# Button.net
KiCad netlist of a schematic drawn in EAGLE
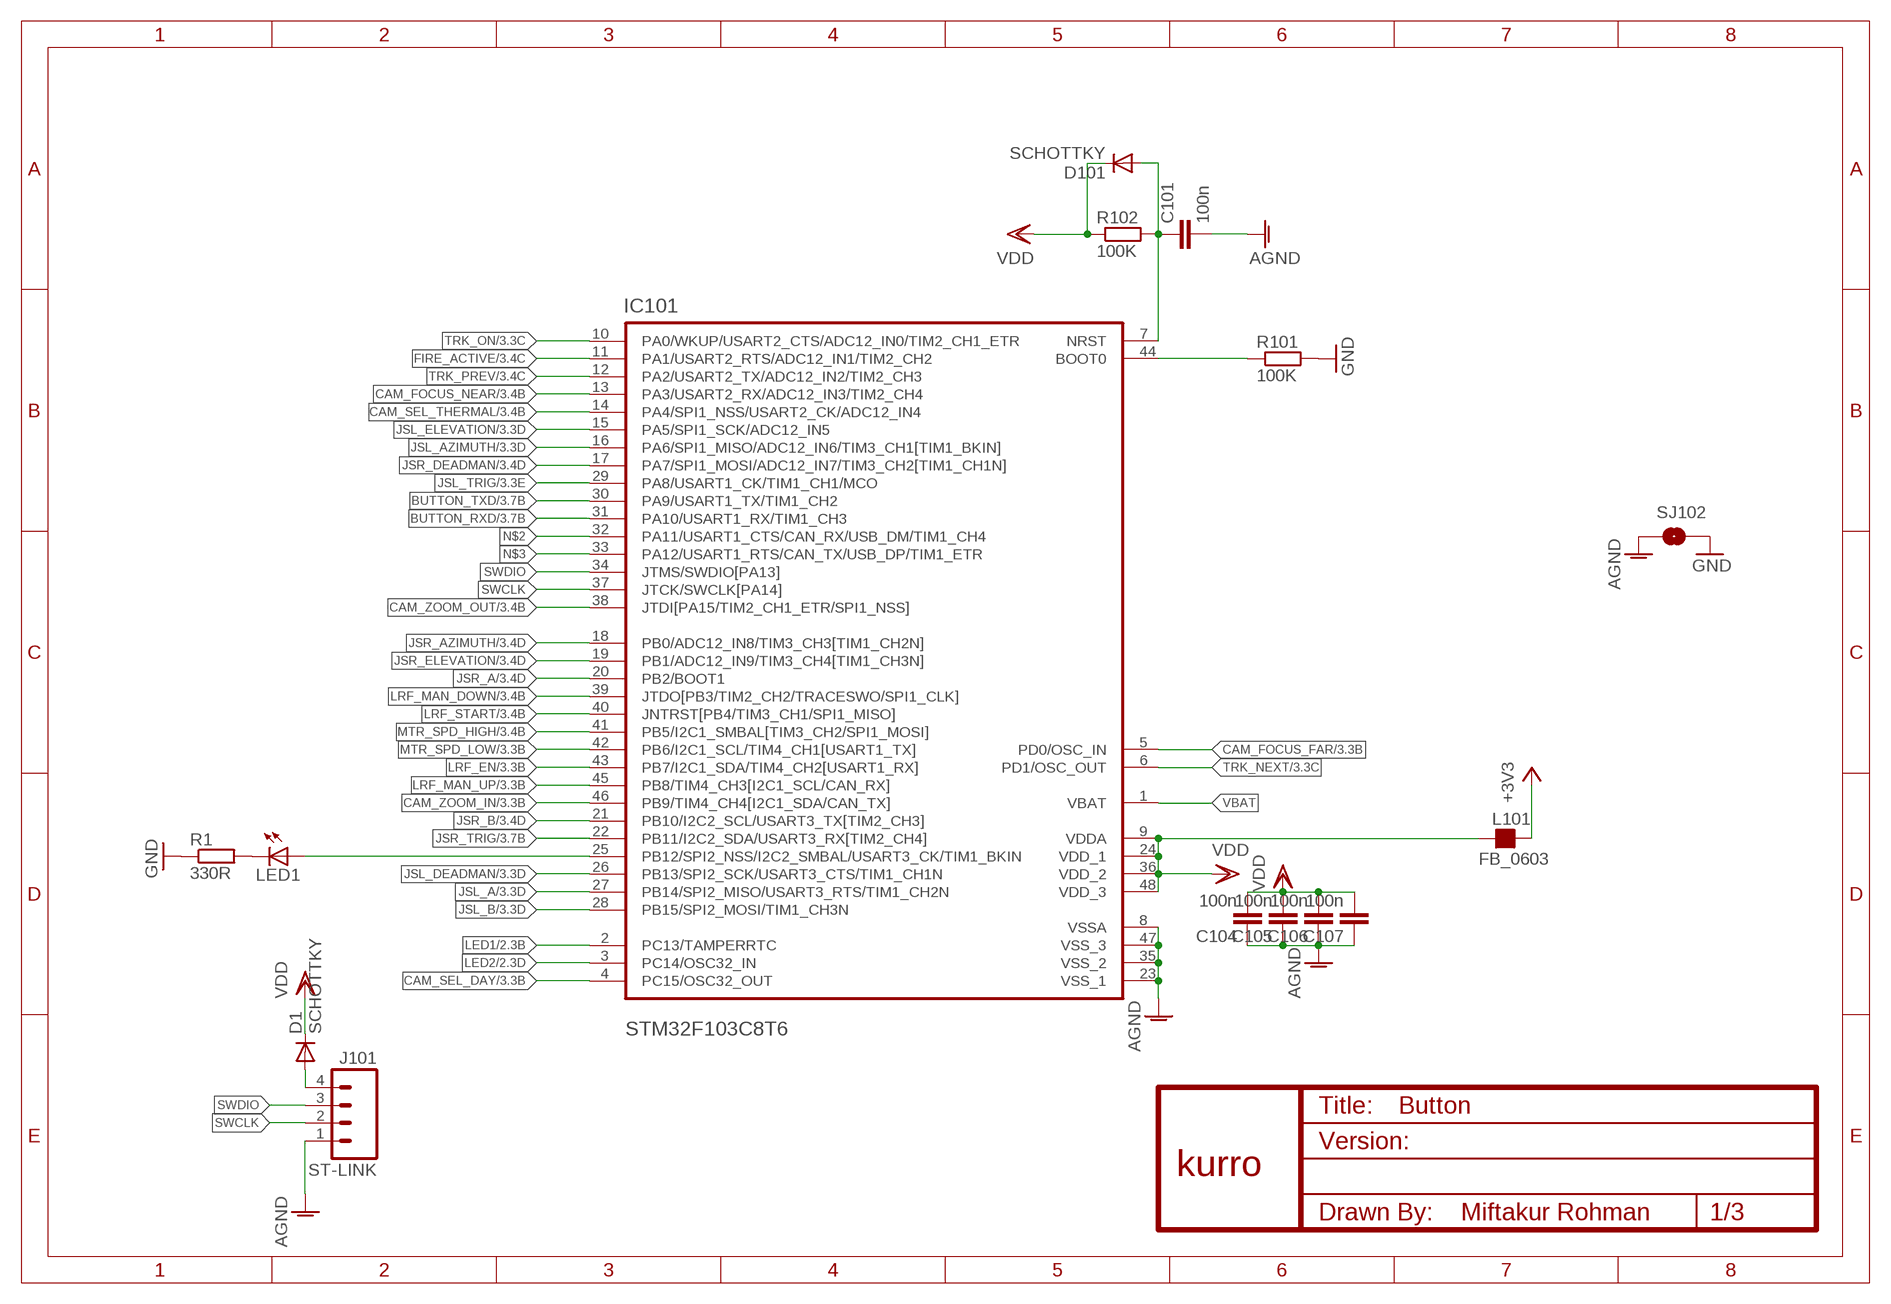
[diagram p0: schematic, sheet 1]
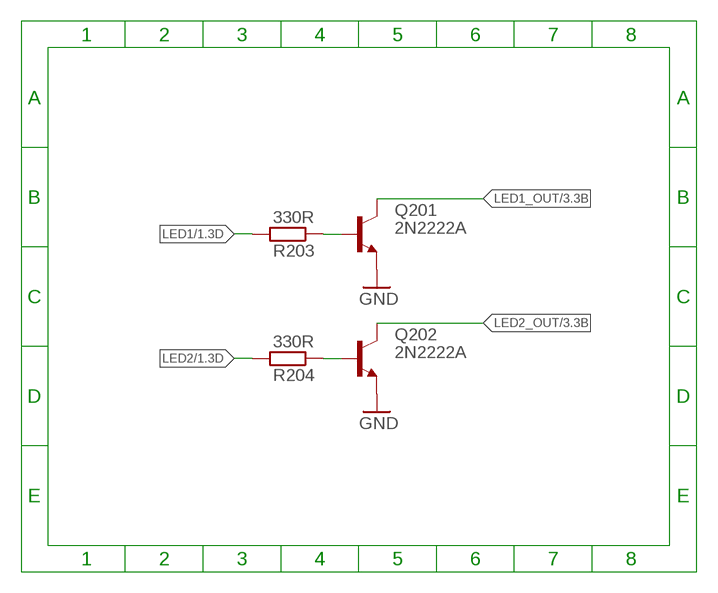
[diagram p1: schematic, sheet 2]
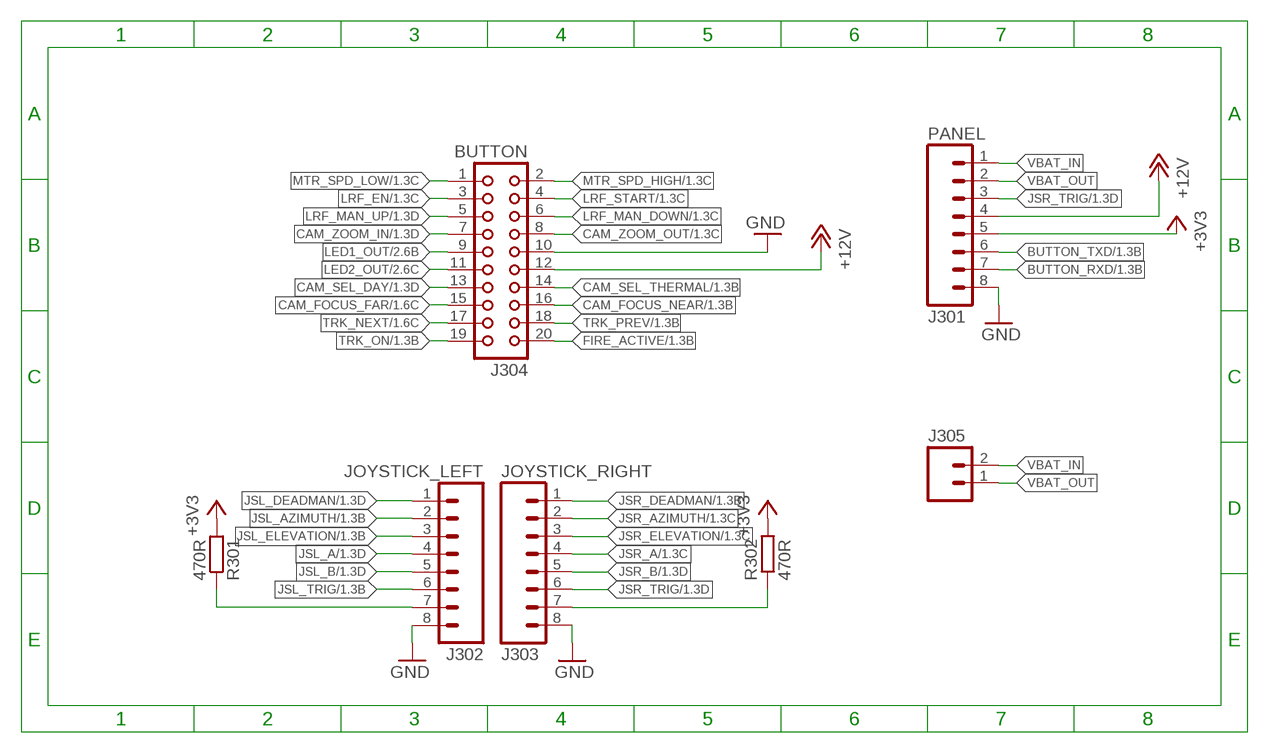
[diagram p2: schematic, sheet 3]

(export (version "E")
  (design (tool "Eeschema 10.0.6"))
  (components
    (comp (ref "Q201")
      (value "2N2222A")
      (footprint "eagle-import:SOT23")
      (libsource (lib "eagle-import") (part "2N2222-REFLOWA"))
    )
    (comp (ref "Q202")
      (value "2N2222A")
      (footprint "eagle-import:SOT23")
      (libsource (lib "eagle-import") (part "2N2222-REFLOWA"))
    )
    (comp (ref "R203")
      (value "330R")
      (footprint "eagle-import:R0603")
      (libsource (lib "eagle-import") (part "R-EU_R0603"))
    )
    (comp (ref "R204")
      (value "330R")
      (footprint "eagle-import:R0603")
      (libsource (lib "eagle-import") (part "R-EU_R0603"))
    )
    (comp (ref "C101")
      (value "100n")
      (footprint "eagle-import:C0603")
      (libsource (lib "eagle-import") (part "C-EUC0603"))
    )
    (comp (ref "C104")
      (value "100n")
      (footprint "eagle-import:C0603")
      (libsource (lib "eagle-import") (part "C-EUC0603"))
    )
    (comp (ref "C105")
      (value "100n")
      (footprint "eagle-import:C0603")
      (libsource (lib "eagle-import") (part "C-EUC0603"))
    )
    (comp (ref "C106")
      (value "100n")
      (footprint "eagle-import:C0603")
      (libsource (lib "eagle-import") (part "C-EUC0603"))
    )
    (comp (ref "C107")
      (value "100n")
      (footprint "eagle-import:C0603")
      (libsource (lib "eagle-import") (part "C-EUC0603"))
    )
    (comp (ref "D1")
      (value "SCHOTTKY")
      (footprint "eagle-import:MICROMELF-W")
      (libsource (lib "eagle-import") (part "DIODE-MICROMELF-W"))
    )
    (comp (ref "D101")
      (value "SCHOTTKY")
      (footprint "eagle-import:MICROMELF-W")
      (libsource (lib "eagle-import") (part "DIODE-MICROMELF-W"))
    )
    (comp (ref "IC101")
      (value "STM32F103C8T6")
      (footprint "eagle-import:QFP50P900X900X160-48N")
      (fields (field (name "MPN") "STM32F103CBT6"))
      (libsource (lib "eagle-import") (part "STM32F103C8T6"))
    )
    (comp (ref "J101")
      (value "ST-LINK")
      (footprint "eagle-import:XH-4-VERT")
      (libsource (lib "eagle-import") (part "M04-XH-VERT"))
    )
    (comp (ref "L101")
      (value "FB_0603")
      (footprint "eagle-import:L0603")
      (libsource (lib "eagle-import") (part "FB_0603"))
    )
    (comp (ref "LED1")
      (value "LED-3MM-NO_SILK")
      (footprint "eagle-import:LED3MM-NS")
      (libsource (lib "eagle-import") (part "LED-3MM-NO_SILK"))
    )
    (comp (ref "R1")
      (value "330R")
      (footprint "eagle-import:R0603")
      (libsource (lib "eagle-import") (part "resistor_R-EU_R0603"))
    )
    (comp (ref "R101")
      (value "100K")
      (footprint "eagle-import:R0603")
      (libsource (lib "eagle-import") (part "resistor_R-EU_R0603"))
    )
    (comp (ref "R102")
      (value "100K")
      (footprint "eagle-import:R0603")
      (libsource (lib "eagle-import") (part "resistor_R-EU_R0603"))
    )
    (comp (ref "SJ102")
      (value "SOLDERJUMPERTRACE")
      (footprint "eagle-import:SJ_2S-TRACE")
      (libsource (lib "eagle-import") (part "SOLDERJUMPERTRACE"))
    )
    (comp (ref "U$1")
      (value "KURRO_FOOTPRINT")
      (footprint "eagle-import:KURRO-LOGO")
      (libsource (lib "eagle-import") (part "KURRO_FOOTPRINT"))
    )
    (comp (ref "J301")
      (value "PANEL")
      (footprint "eagle-import:XH-8-RA")
      (libsource (lib "eagle-import") (part "M08-XH-RA"))
    )
    (comp (ref "J302")
      (value "JOYSTICK_LEFT")
      (footprint "eagle-import:XH-8-RA")
      (libsource (lib "eagle-import") (part "M08-XH-RA"))
    )
    (comp (ref "J303")
      (value "JOYSTICK_RIGHT")
      (footprint "eagle-import:XH-8-RA")
      (libsource (lib "eagle-import") (part "M08-XH-RA"))
    )
    (comp (ref "J304")
      (value "BUTTON")
      (footprint "eagle-import:CON20")
      (libsource (lib "eagle-import") (part "CON20"))
    )
    (comp (ref "J305")
      (value "M02-XH-RA")
      (footprint "eagle-import:XH-2-RA")
      (libsource (lib "eagle-import") (part "M02-XH-RA"))
    )
    (comp (ref "R301")
      (value "470R")
      (footprint "eagle-import:R0603")
      (libsource (lib "eagle-import") (part "R-EU_R0603"))
    )
    (comp (ref "R302")
      (value "470R")
      (footprint "eagle-import:R0603")
      (libsource (lib "eagle-import") (part "R-EU_R0603"))
    )
  )
  (nets
    (net (code "1") (name "+3V3") (class "Default")
      (node (ref "J301") (pin "5") (pinfunction "5_5") (pintype "passive"))
      (node (ref "L101") (pin "2") (pinfunction "2_2") (pintype "passive"))
      (node (ref "R301") (pin "2") (pinfunction "2_2") (pintype "passive"))
      (node (ref "R302") (pin "2") (pinfunction "2_2") (pintype "passive"))
    )
    (net (code "2") (name "+12V") (class "Default")
      (node (ref "J301") (pin "4") (pinfunction "4_4") (pintype "passive"))
      (node (ref "J304") (pin "12") (pinfunction "12_12") (pintype "passive"))
    )
    (net (code "3") (name "AGND") (class "Default")
      (node (ref "C101") (pin "2") (pinfunction "2_2") (pintype "passive"))
      (node (ref "C104") (pin "1") (pinfunction "1_1") (pintype "passive"))
      (node (ref "C105") (pin "1") (pinfunction "1_1") (pintype "passive"))
      (node (ref "C106") (pin "1") (pinfunction "1_1") (pintype "passive"))
      (node (ref "C107") (pin "1") (pinfunction "1_1") (pintype "passive"))
      (node (ref "IC101") (pin "23") (pinfunction "VSS_1_23") (pintype "bidirectional"))
      (node (ref "IC101") (pin "35") (pinfunction "VSS_2_35") (pintype "passive"))
      (node (ref "IC101") (pin "47") (pinfunction "VSS_3_47") (pintype "passive"))
      (node (ref "IC101") (pin "8") (pinfunction "VSSA_8") (pintype "passive"))
      (node (ref "J101") (pin "1") (pinfunction "1_1") (pintype "passive"))
      (node (ref "SJ102") (pin "1") (pinfunction "1_1") (pintype "passive"))
    )
    (net (code "4") (name "BUTTON_RXD") (class "Default")
      (node (ref "IC101") (pin "31") (pinfunction "PA10/USART1_RX/TIM1_CH3_31") (pintype "bidirectional"))
      (node (ref "J301") (pin "7") (pinfunction "7_7") (pintype "passive"))
    )
    (net (code "5") (name "BUTTON_TXD") (class "Default")
      (node (ref "IC101") (pin "30") (pinfunction "PA9/USART1_TX/TIM1_CH2_30") (pintype "bidirectional"))
      (node (ref "J301") (pin "6") (pinfunction "6_6") (pintype "passive"))
    )
    (net (code "6") (name "CAM_FOCUS_FAR") (class "Default")
      (node (ref "IC101") (pin "5") (pinfunction "PD0/OSC_IN_5") (pintype "bidirectional"))
      (node (ref "J304") (pin "15") (pinfunction "15_15") (pintype "passive"))
    )
    (net (code "7") (name "CAM_FOCUS_NEAR") (class "Default")
      (node (ref "IC101") (pin "13") (pinfunction "PA3/USART2_RX/ADC12_IN3/TIM2_CH4_13") (pintype "bidirectional"))
      (node (ref "J304") (pin "16") (pinfunction "16_16") (pintype "passive"))
    )
    (net (code "8") (name "CAM_SEL_DAY") (class "Default")
      (node (ref "IC101") (pin "4") (pinfunction "PC15/OSC32_OUT_4") (pintype "bidirectional"))
      (node (ref "J304") (pin "13") (pinfunction "13_13") (pintype "passive"))
    )
    (net (code "9") (name "CAM_SEL_THERMAL") (class "Default")
      (node (ref "IC101") (pin "14") (pinfunction "PA4/SPI1_NSS/USART2_CK/ADC12_IN4_14") (pintype "bidirectional"))
      (node (ref "J304") (pin "14") (pinfunction "14_14") (pintype "passive"))
    )
    (net (code "10") (name "CAM_ZOOM_IN") (class "Default")
      (node (ref "IC101") (pin "46") (pinfunction "PB9/TIM4_CH4[I2C1_SDA/CAN_TX]_46") (pintype "bidirectional"))
      (node (ref "J304") (pin "7") (pinfunction "7_7") (pintype "passive"))
    )
    (net (code "11") (name "CAM_ZOOM_OUT") (class "Default")
      (node (ref "IC101") (pin "38") (pinfunction "JTDI[PA15/TIM2_CH1_ETR/SPI1_NSS]_38") (pintype "bidirectional"))
      (node (ref "J304") (pin "8") (pinfunction "8_8") (pintype "passive"))
    )
    (net (code "12") (name "FIRE_ACTIVE") (class "Default")
      (node (ref "IC101") (pin "11") (pinfunction "PA1/USART2_RTS/ADC12_IN1/TIM2_CH2_11") (pintype "bidirectional"))
      (node (ref "J304") (pin "20") (pinfunction "20_20") (pintype "passive"))
    )
    (net (code "13") (name "GND") (class "Default")
      (node (ref "J301") (pin "8") (pinfunction "8_8") (pintype "passive"))
      (node (ref "J302") (pin "8") (pinfunction "8_8") (pintype "passive"))
      (node (ref "J303") (pin "8") (pinfunction "8_8") (pintype "passive"))
      (node (ref "J304") (pin "10") (pinfunction "10_10") (pintype "passive"))
      (node (ref "Q201") (pin "2") (pinfunction "E_2") (pintype "passive"))
      (node (ref "Q202") (pin "2") (pinfunction "E_2") (pintype "passive"))
      (node (ref "R1") (pin "1") (pinfunction "1_1") (pintype "passive"))
      (node (ref "R101") (pin "2") (pinfunction "2_2") (pintype "passive"))
      (node (ref "SJ102") (pin "2") (pinfunction "2_2") (pintype "passive"))
    )
    (net (code "14") (name "JSL_A") (class "Default")
      (node (ref "IC101") (pin "27") (pinfunction "PB14/SPI2_MISO/USART3_RTS/TIM1_CH2N_27") (pintype "bidirectional"))
      (node (ref "J302") (pin "4") (pinfunction "4_4") (pintype "passive"))
    )
    (net (code "15") (name "JSL_AZIMUTH") (class "Default")
      (node (ref "IC101") (pin "16") (pinfunction "PA6/SPI1_MISO/ADC12_IN6/TIM3_CH1[TIM1_BKIN]_16") (pintype "bidirectional"))
      (node (ref "J302") (pin "2") (pinfunction "2_2") (pintype "passive"))
    )
    (net (code "16") (name "JSL_B") (class "Default")
      (node (ref "IC101") (pin "28") (pinfunction "PB15/SPI2_MOSI/TIM1_CH3N_28") (pintype "bidirectional"))
      (node (ref "J302") (pin "5") (pinfunction "5_5") (pintype "passive"))
    )
    (net (code "17") (name "JSL_DEADMAN") (class "Default")
      (node (ref "IC101") (pin "26") (pinfunction "PB13/SPI2_SCK/USART3_CTS/TIM1_CH1N_26") (pintype "bidirectional"))
      (node (ref "J302") (pin "1") (pinfunction "1_1") (pintype "passive"))
    )
    (net (code "18") (name "JSL_ELEVATION") (class "Default")
      (node (ref "IC101") (pin "15") (pinfunction "PA5/SPI1_SCK/ADC12_IN5_15") (pintype "bidirectional"))
      (node (ref "J302") (pin "3") (pinfunction "3_3") (pintype "passive"))
    )
    (net (code "19") (name "JSL_TRIG") (class "Default")
      (node (ref "IC101") (pin "29") (pinfunction "PA8/USART1_CK/TIM1_CH1/MCO_29") (pintype "bidirectional"))
      (node (ref "J302") (pin "6") (pinfunction "6_6") (pintype "passive"))
    )
    (net (code "20") (name "JSR_A") (class "Default")
      (node (ref "IC101") (pin "20") (pinfunction "PB2/BOOT1_20") (pintype "bidirectional"))
      (node (ref "J303") (pin "4") (pinfunction "4_4") (pintype "passive"))
    )
    (net (code "21") (name "JSR_AZIMUTH") (class "Default")
      (node (ref "IC101") (pin "18") (pinfunction "PB0/ADC12_IN8/TIM3_CH3[TIM1_CH2N]_18") (pintype "bidirectional"))
      (node (ref "J303") (pin "2") (pinfunction "2_2") (pintype "passive"))
    )
    (net (code "22") (name "JSR_B") (class "Default")
      (node (ref "IC101") (pin "21") (pinfunction "PB10/I2C2_SCL/USART3_TX[TIM2_CH3]_21") (pintype "bidirectional"))
      (node (ref "J303") (pin "5") (pinfunction "5_5") (pintype "passive"))
    )
    (net (code "23") (name "JSR_DEADMAN") (class "Default")
      (node (ref "IC101") (pin "17") (pinfunction "PA7/SPI1_MOSI/ADC12_IN7/TIM3_CH2[TIM1_CH1N]_17") (pintype "bidirectional"))
      (node (ref "J303") (pin "1") (pinfunction "1_1") (pintype "passive"))
    )
    (net (code "24") (name "JSR_ELEVATION") (class "Default")
      (node (ref "IC101") (pin "19") (pinfunction "PB1/ADC12_IN9/TIM3_CH4[TIM1_CH3N]_19") (pintype "bidirectional"))
      (node (ref "J303") (pin "3") (pinfunction "3_3") (pintype "passive"))
    )
    (net (code "25") (name "JSR_TRIG") (class "Default")
      (node (ref "IC101") (pin "22") (pinfunction "PB11/I2C2_SDA/USART3_RX[TIM2_CH4]_22") (pintype "bidirectional"))
      (node (ref "J301") (pin "3") (pinfunction "3_3") (pintype "passive"))
      (node (ref "J303") (pin "6") (pinfunction "6_6") (pintype "passive"))
    )
    (net (code "26") (name "LED1") (class "Default")
      (node (ref "IC101") (pin "2") (pinfunction "PC13/TAMPERRTC_2") (pintype "bidirectional"))
      (node (ref "R203") (pin "2") (pinfunction "2_2") (pintype "passive"))
    )
    (net (code "27") (name "LED1_OUT") (class "Default")
      (node (ref "J304") (pin "9") (pinfunction "9_9") (pintype "passive"))
      (node (ref "Q201") (pin "3") (pinfunction "C_3") (pintype "passive"))
    )
    (net (code "28") (name "LED2") (class "Default")
      (node (ref "IC101") (pin "3") (pinfunction "PC14/OSC32_IN_3") (pintype "bidirectional"))
      (node (ref "R204") (pin "2") (pinfunction "2_2") (pintype "passive"))
    )
    (net (code "29") (name "LED2_OUT") (class "Default")
      (node (ref "J304") (pin "11") (pinfunction "11_11") (pintype "passive"))
      (node (ref "Q202") (pin "3") (pinfunction "C_3") (pintype "passive"))
    )
    (net (code "30") (name "LRF_EN") (class "Default")
      (node (ref "IC101") (pin "43") (pinfunction "PB7/I2C1_SDA/TIM4_CH2[USART1_RX]_43") (pintype "bidirectional"))
      (node (ref "J304") (pin "3") (pinfunction "3_3") (pintype "passive"))
    )
    (net (code "31") (name "LRF_MAN_DOWN") (class "Default")
      (node (ref "IC101") (pin "39") (pinfunction "JTDO[PB3/TIM2_CH2/TRACESWO/SPI1_CLK]_39") (pintype "bidirectional"))
      (node (ref "J304") (pin "6") (pinfunction "6_6") (pintype "passive"))
    )
    (net (code "32") (name "LRF_MAN_UP") (class "Default")
      (node (ref "IC101") (pin "45") (pinfunction "PB8/TIM4_CH3[I2C1_SCL/CAN_RX]_45") (pintype "bidirectional"))
      (node (ref "J304") (pin "5") (pinfunction "5_5") (pintype "passive"))
    )
    (net (code "33") (name "LRF_START") (class "Default")
      (node (ref "IC101") (pin "40") (pinfunction "JNTRST[PB4/TIM3_CH1/SPI1_MISO]_40") (pintype "bidirectional"))
      (node (ref "J304") (pin "4") (pinfunction "4_4") (pintype "passive"))
    )
    (net (code "34") (name "MTR_SPD_HIGH") (class "Default")
      (node (ref "IC101") (pin "41") (pinfunction "PB5/I2C1_SMBAL[TIM3_CH2/SPI1_MOSI]_41") (pintype "bidirectional"))
      (node (ref "J304") (pin "2") (pinfunction "2_2") (pintype "passive"))
    )
    (net (code "35") (name "MTR_SPD_LOW") (class "Default")
      (node (ref "IC101") (pin "42") (pinfunction "PB6/I2C1_SCL/TIM4_CH1[USART1_TX]_42") (pintype "bidirectional"))
      (node (ref "J304") (pin "1") (pinfunction "1_1") (pintype "passive"))
    )
    (net (code "36") (name "N$2") (class "Default")
      (node (ref "IC101") (pin "32") (pinfunction "PA11/USART1_CTS/CAN_RX/USB_DM/TIM1_CH4_32") (pintype "power_in"))
    )
    (net (code "37") (name "N$3") (class "Default")
      (node (ref "IC101") (pin "33") (pinfunction "PA12/USART1_RTS/CAN_TX/USB_DP/TIM1_ETR_33") (pintype "bidirectional"))
    )
    (net (code "38") (name "Net-(D1-PadA)") (class "Default")
      (node (ref "D1") (pin "A") (pinfunction "A_A") (pintype "passive"))
      (node (ref "J101") (pin "4") (pinfunction "4_4") (pintype "passive"))
    )
    (net (code "39") (name "Net-(IC101-BOOT0)") (class "Default")
      (node (ref "IC101") (pin "44") (pinfunction "BOOT0_44") (pintype "bidirectional"))
      (node (ref "R101") (pin "1") (pinfunction "1_1") (pintype "passive"))
    )
    (net (code "40") (name "Net-(IC101-NRST)") (class "Default")
      (node (ref "C101") (pin "1") (pinfunction "1_1") (pintype "passive"))
      (node (ref "D101") (pin "A") (pinfunction "A_A") (pintype "passive"))
      (node (ref "IC101") (pin "7") (pinfunction "NRST_7") (pintype "bidirectional"))
      (node (ref "R102") (pin "2") (pinfunction "2_2") (pintype "passive"))
    )
    (net (code "41") (name "Net-(IC101-PB12{slash}SPI2_NSS{slash}I2C2_SMBAL{slash}USART3_CK{slash}TIM1_BKIN)") (class "Default")
      (node (ref "IC101") (pin "25") (pinfunction "PB12/SPI2_NSS/I2C2_SMBAL/USART3_CK/TIM1_BKIN_25") (pintype "bidirectional"))
      (node (ref "LED1") (pin "A") (pinfunction "A_A") (pintype "passive"))
    )
    (net (code "42") (name "Net-(J302-Pad7)") (class "Default")
      (node (ref "J302") (pin "7") (pinfunction "7_7") (pintype "passive"))
      (node (ref "R301") (pin "1") (pinfunction "1_1") (pintype "passive"))
    )
    (net (code "43") (name "Net-(J303-Pad7)") (class "Default")
      (node (ref "J303") (pin "7") (pinfunction "7_7") (pintype "passive"))
      (node (ref "R302") (pin "1") (pinfunction "1_1") (pintype "passive"))
    )
    (net (code "44") (name "Net-(LED1-C)") (class "Default")
      (node (ref "LED1") (pin "K") (pinfunction "C_K") (pintype "passive"))
      (node (ref "R1") (pin "2") (pinfunction "2_2") (pintype "passive"))
    )
    (net (code "45") (name "Net-(Q201-B)") (class "Default")
      (node (ref "Q201") (pin "1") (pinfunction "B_1") (pintype "passive"))
      (node (ref "R203") (pin "1") (pinfunction "1_1") (pintype "passive"))
    )
    (net (code "46") (name "Net-(Q202-B)") (class "Default")
      (node (ref "Q202") (pin "1") (pinfunction "B_1") (pintype "passive"))
      (node (ref "R204") (pin "1") (pinfunction "1_1") (pintype "passive"))
    )
    (net (code "47") (name "SWCLK") (class "Default")
      (node (ref "IC101") (pin "37") (pinfunction "JTCK/SWCLK[PA14]_37") (pintype "bidirectional"))
      (node (ref "J101") (pin "2") (pinfunction "2_2") (pintype "passive"))
    )
    (net (code "48") (name "SWDIO") (class "Default")
      (node (ref "IC101") (pin "34") (pinfunction "JTMS/SWDIO[PA13]_34") (pintype "bidirectional"))
      (node (ref "J101") (pin "3") (pinfunction "3_3") (pintype "passive"))
    )
    (net (code "49") (name "TRK_NEXT") (class "Default")
      (node (ref "IC101") (pin "6") (pinfunction "PD1/OSC_OUT_6") (pintype "bidirectional"))
      (node (ref "J304") (pin "17") (pinfunction "17_17") (pintype "passive"))
    )
    (net (code "50") (name "TRK_ON") (class "Default")
      (node (ref "IC101") (pin "10") (pinfunction "PA0/WKUP/USART2_CTS/ADC12_IN0/TIM2_CH1_ETR_10") (pintype "bidirectional"))
      (node (ref "J304") (pin "19") (pinfunction "19_19") (pintype "passive"))
    )
    (net (code "51") (name "TRK_PREV") (class "Default")
      (node (ref "IC101") (pin "12") (pinfunction "PA2/USART2_TX/ADC12_IN2/TIM2_CH3_12") (pintype "bidirectional"))
      (node (ref "J304") (pin "18") (pinfunction "18_18") (pintype "passive"))
    )
    (net (code "52") (name "VBAT") (class "Default")
      (node (ref "IC101") (pin "1") (pinfunction "VBAT_1") (pintype "input"))
    )
    (net (code "53") (name "VBAT_IN") (class "Default")
      (node (ref "J301") (pin "1") (pinfunction "1_1") (pintype "passive"))
      (node (ref "J305") (pin "2") (pinfunction "2_2") (pintype "passive"))
    )
    (net (code "54") (name "VBAT_OUT") (class "Default")
      (node (ref "J301") (pin "2") (pinfunction "2_2") (pintype "passive"))
      (node (ref "J305") (pin "1") (pinfunction "1_1") (pintype "passive"))
    )
    (net (code "55") (name "VDD") (class "Default")
      (node (ref "C104") (pin "2") (pinfunction "2_2") (pintype "passive"))
      (node (ref "C105") (pin "2") (pinfunction "2_2") (pintype "passive"))
      (node (ref "C106") (pin "2") (pinfunction "2_2") (pintype "passive"))
      (node (ref "C107") (pin "2") (pinfunction "2_2") (pintype "passive"))
      (node (ref "D1") (pin "C") (pinfunction "C_C") (pintype "passive"))
      (node (ref "D101") (pin "C") (pinfunction "C_C") (pintype "passive"))
      (node (ref "IC101") (pin "24") (pinfunction "VDD_1_24") (pintype "bidirectional"))
      (node (ref "IC101") (pin "36") (pinfunction "VDD_2_36") (pintype "power_in"))
      (node (ref "IC101") (pin "48") (pinfunction "VDD_3_48") (pintype "power_in"))
      (node (ref "IC101") (pin "9") (pinfunction "VDDA_9") (pintype "power_in"))
      (node (ref "L101") (pin "1") (pinfunction "1_1") (pintype "passive"))
      (node (ref "R102") (pin "1") (pinfunction "1_1") (pintype "passive"))
    )
  )
)
